# in9-test-board-v1.net
KiCad netlist of a schematic drawn in EAGLE
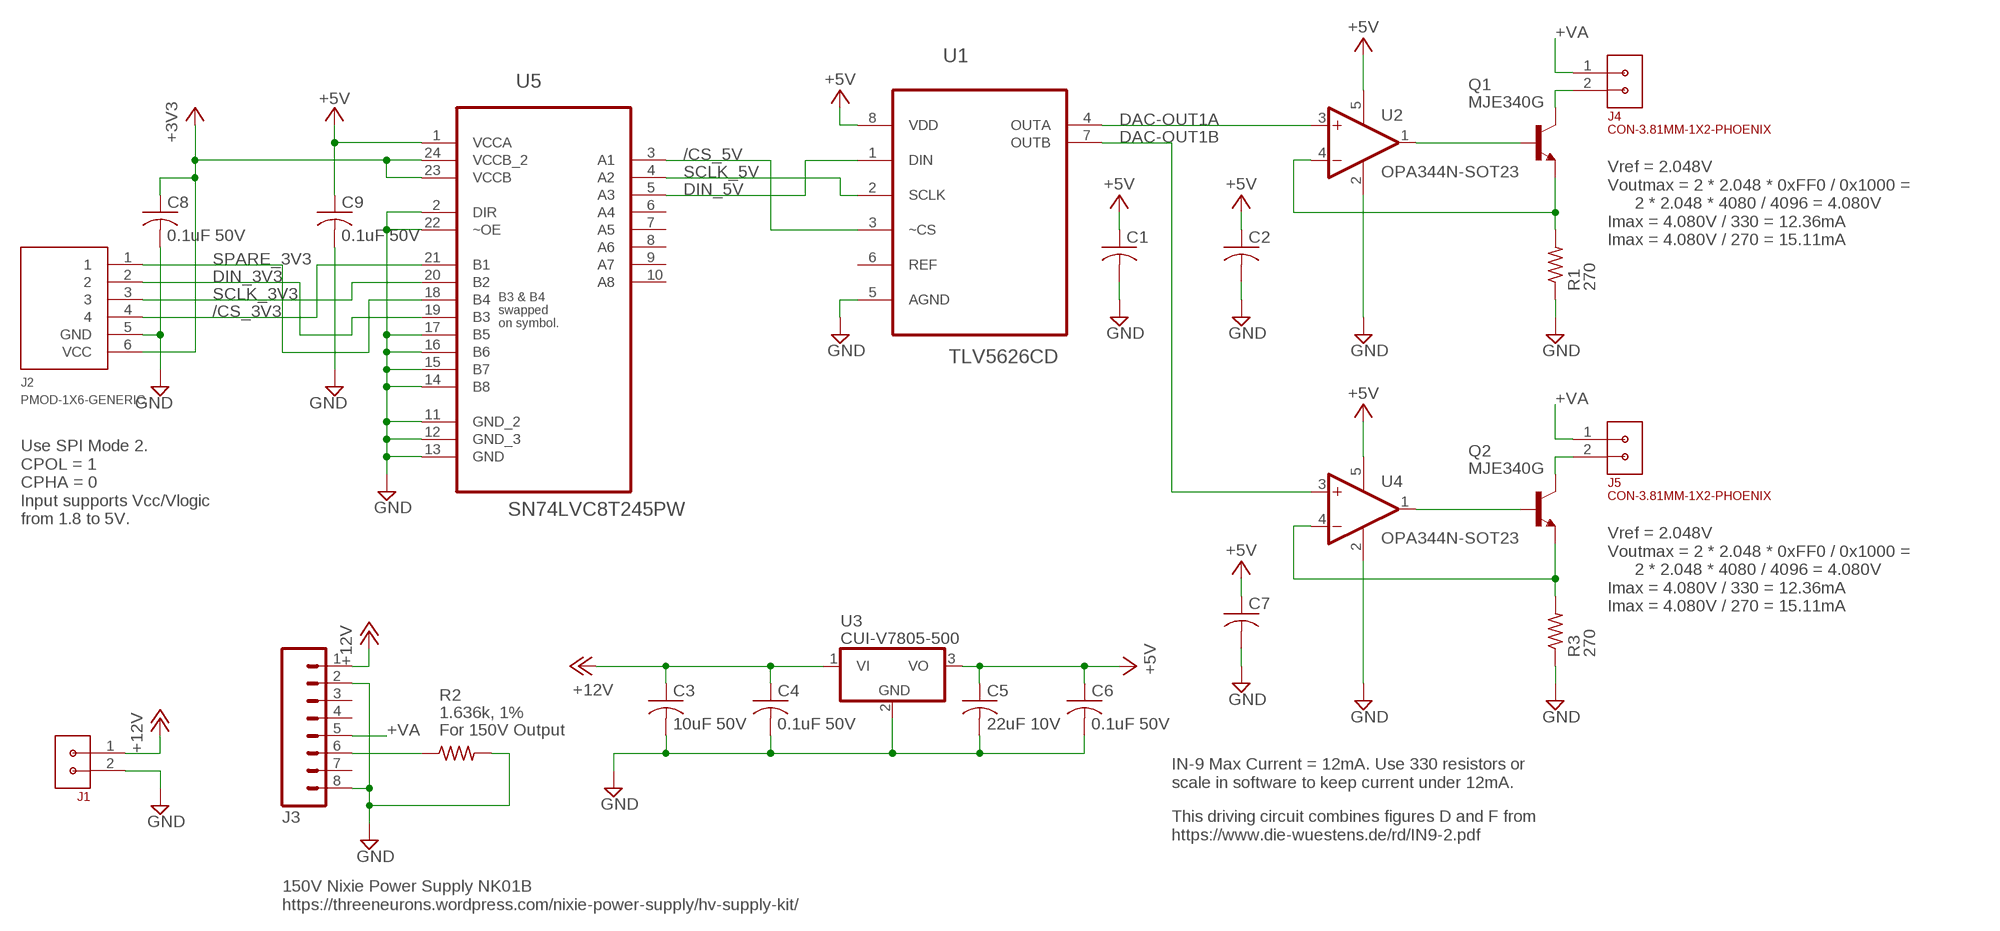
[diagram p0: schematic, sheet 1]

(export (version "E")
  (design (tool "Eeschema 10.0.6"))
  (components
    (comp (ref "C1")
      (value "C-USC1206K")
      (footprint "eagle-import:C1206K")
      (libsource (lib "eagle-import") (part "C-USC1206K"))
    )
    (comp (ref "C2")
      (value "C-USC1206K")
      (footprint "eagle-import:C1206K")
      (libsource (lib "eagle-import") (part "C-USC1206K"))
    )
    (comp (ref "C3")
      (value "10uF 50V")
      (footprint "eagle-import:C1210K")
      (fields (field (name "MFR") "KEMET") (field (name "MFR_PART_NO") "C1210C106K5RACTU"))
      (libsource (lib "eagle-import") (part "C-USC1210K"))
    )
    (comp (ref "C4")
      (value "0.1uF 50V")
      (footprint "eagle-import:C1206K")
      (fields (field (name "MFR") "KEMET") (field (name "MFR_PART_NO") "C1206S104M5RACTU"))
      (libsource (lib "eagle-import") (part "C-USC1206K"))
    )
    (comp (ref "C5")
      (value "22uF 10V")
      (footprint "eagle-import:C1206K")
      (fields (field (name "MFR") "KEMET") (field (name "MFR_PART_NO") "C1206C226K8RAC7800"))
      (libsource (lib "eagle-import") (part "C-USC1206K"))
    )
    (comp (ref "C6")
      (value "0.1uF 50V")
      (footprint "eagle-import:C1206K")
      (fields (field (name "MFR") "KEMET") (field (name "MFR_PART_NO") "C1206S104M5RACTU"))
      (libsource (lib "eagle-import") (part "C-USC1206K"))
    )
    (comp (ref "C7")
      (value "C-USC1206K")
      (footprint "eagle-import:C1206K")
      (libsource (lib "eagle-import") (part "C-USC1206K"))
    )
    (comp (ref "C8")
      (value "0.1uF 50V")
      (footprint "eagle-import:C1206K")
      (fields (field (name "MFR") "KEMET") (field (name "MFR_PART_NO") "C1206S104M5RACTU"))
      (libsource (lib "eagle-import") (part "C-USC1206K"))
    )
    (comp (ref "C9")
      (value "0.1uF 50V")
      (footprint "eagle-import:C1206K")
      (fields (field (name "MFR") "KEMET") (field (name "MFR_PART_NO") "C1206S104M5RACTU"))
      (libsource (lib "eagle-import") (part "C-USC1206K"))
    )
    (comp (ref "J1")
      (value "CON-3.81MM-1X2-PHOENIX-1803426")
      (footprint "eagle-import:CON-PHOENIX-1803426-3.81-1X2")
      (libsource (lib "eagle-import") (part "CON-3.81MM-1X2-PHOENIX-1803426"))
    )
    (comp (ref "J2")
      (value "PMOD-1X6-GENERIC")
      (footprint "eagle-import:CON-PMOD-1X6")
      (libsource (lib "eagle-import") (part "PMOD-1X6-GENERIC"))
    )
    (comp (ref "J3")
      (value "M08")
      (footprint "eagle-import:1X08")
      (libsource (lib "eagle-import") (part "M08"))
    )
    (comp (ref "J4")
      (value "CON-3.81MM-1X2-PHOENIX")
      (footprint "eagle-import:CON-PHOENIX-3.81-1X2-RA")
      (libsource (lib "eagle-import") (part "CON-3.81MM-1X2-PHOENIX"))
    )
    (comp (ref "J5")
      (value "CON-3.81MM-1X2-PHOENIX")
      (footprint "eagle-import:CON-PHOENIX-3.81-1X2-RA")
      (libsource (lib "eagle-import") (part "CON-3.81MM-1X2-PHOENIX"))
    )
    (comp (ref "Q1")
      (value "MJE340G")
      (footprint "eagle-import:TO126V")
      (libsource (lib "eagle-import") (part "-NPN-TO126V"))
    )
    (comp (ref "Q2")
      (value "MJE340G")
      (footprint "eagle-import:TO126V")
      (libsource (lib "eagle-import") (part "-NPN-TO126V"))
    )
    (comp (ref "R1")
      (value "270")
      (footprint "eagle-import:R1206")
      (libsource (lib "eagle-import") (part "R-US_R1206"))
    )
    (comp (ref "R2")
      (value "1.636k, 1%")
      (footprint "eagle-import:R1206")
      (libsource (lib "eagle-import") (part "R-US_R1206"))
    )
    (comp (ref "R3")
      (value "270")
      (footprint "eagle-import:R1206")
      (libsource (lib "eagle-import") (part "R-US_R1206"))
    )
    (comp (ref "U1")
      (value "TLV5626CD")
      (footprint "eagle-import:SOIC127P600X175-8N")
      (libsource (lib "eagle-import") (part "TLV5626CD"))
    )
    (comp (ref "U2")
      (value "OPA344N-SOT23")
      (footprint "eagle-import:SOT23-5")
      (libsource (lib "eagle-import") (part "OPA-SOT23344N"))
    )
    (comp (ref "U3")
      (value "CUI-V7805-500")
      (footprint "eagle-import:CUI-78XX-500")
      (libsource (lib "eagle-import") (part "CUI-V7803-500"))
    )
    (comp (ref "U4")
      (value "OPA344N-SOT23")
      (footprint "eagle-import:SOT23-5")
      (libsource (lib "eagle-import") (part "OPA-SOT23344N"))
    )
    (comp (ref "U5")
      (value "SN74LVC8T245PW")
      (footprint "eagle-import:SOP65P640X120-24N")
      (fields (field (name "MPN") "SN74AVC8T245PW"))
      (libsource (lib "eagle-import") (part "SN74AVC8T245PW"))
    )
  )
  (nets
    (net (code "1") (name "+3V3") (class "Default")
      (node (ref "C8") (pin "1") (pinfunction "1_1") (pintype "passive"))
      (node (ref "J2") (pin "6") (pinfunction "VCC_6") (pintype "bidirectional"))
      (node (ref "U5") (pin "23") (pinfunction "VCCB_23") (pintype "power_in"))
      (node (ref "U5") (pin "24") (pinfunction "VCCB_2_24") (pintype "power_in"))
    )
    (net (code "2") (name "+5V") (class "Default")
      (node (ref "C1") (pin "1") (pinfunction "1_1") (pintype "passive"))
      (node (ref "C2") (pin "1") (pinfunction "1_1") (pintype "passive"))
      (node (ref "C5") (pin "1") (pinfunction "1_1") (pintype "passive"))
      (node (ref "C6") (pin "1") (pinfunction "1_1") (pintype "passive"))
      (node (ref "C7") (pin "1") (pinfunction "1_1") (pintype "passive"))
      (node (ref "C9") (pin "1") (pinfunction "1_1") (pintype "passive"))
      (node (ref "U1") (pin "8") (pinfunction "VDD_8") (pintype "power_in"))
      (node (ref "U2") (pin "5") (pinfunction "V+_5") (pintype "power_in"))
      (node (ref "U3") (pin "3") (pinfunction "VO_3") (pintype "passive"))
      (node (ref "U4") (pin "5") (pinfunction "V+_5") (pintype "power_in"))
      (node (ref "U5") (pin "1") (pinfunction "VCCA_1") (pintype "power_in"))
    )
    (net (code "3") (name "+12V") (class "Default")
      (node (ref "C3") (pin "1") (pinfunction "1_1") (pintype "passive"))
      (node (ref "C4") (pin "1") (pinfunction "1_1") (pintype "passive"))
      (node (ref "J1") (pin "1") (pinfunction "1_1") (pintype "bidirectional"))
      (node (ref "J3") (pin "1") (pinfunction "1_1") (pintype "passive"))
      (node (ref "U3") (pin "1") (pinfunction "VI_1") (pintype "input"))
    )
    (net (code "4") (name "/+VA") (class "Default")
      (node (ref "J3") (pin "5") (pinfunction "5_5") (pintype "passive"))
      (node (ref "J4") (pin "1") (pinfunction "1_1") (pintype "bidirectional"))
      (node (ref "J5") (pin "1") (pinfunction "1_1") (pintype "bidirectional"))
    )
    (net (code "5") (name "/DAC-OUT1A") (class "Default")
      (node (ref "U1") (pin "4") (pinfunction "OUTA_4") (pintype "output"))
      (node (ref "U2") (pin "3") (pinfunction "+IN_3") (pintype "input"))
    )
    (net (code "6") (name "/DAC-OUT1B") (class "Default")
      (node (ref "U1") (pin "7") (pinfunction "OUTB_7") (pintype "output"))
      (node (ref "U4") (pin "3") (pinfunction "+IN_3") (pintype "input"))
    )
    (net (code "7") (name "/DIN_3V3") (class "Default")
      (node (ref "J2") (pin "2") (pinfunction "2_2") (pintype "bidirectional"))
      (node (ref "U5") (pin "19") (pinfunction "B3_19") (pintype "bidirectional"))
    )
    (net (code "8") (name "/DIN_5V") (class "Default")
      (node (ref "U1") (pin "1") (pinfunction "DIN_1") (pintype "input"))
      (node (ref "U5") (pin "5") (pinfunction "A3_5") (pintype "bidirectional"))
    )
    (net (code "9") (name "/SCLK_3V3") (class "Default")
      (node (ref "J2") (pin "3") (pinfunction "3_3") (pintype "bidirectional"))
      (node (ref "U5") (pin "20") (pinfunction "B2_20") (pintype "bidirectional"))
    )
    (net (code "10") (name "/SCLK_5V") (class "Default")
      (node (ref "U1") (pin "2") (pinfunction "SCLK_2") (pintype "input"))
      (node (ref "U5") (pin "4") (pinfunction "A2_4") (pintype "bidirectional"))
    )
    (net (code "11") (name "/SPARE_3V3") (class "Default")
      (node (ref "J2") (pin "1") (pinfunction "1_1") (pintype "bidirectional"))
      (node (ref "U5") (pin "18") (pinfunction "B4_18") (pintype "bidirectional"))
    )
    (net (code "12") (name "/{slash}CS_3V3") (class "Default")
      (node (ref "J2") (pin "4") (pinfunction "4_4") (pintype "bidirectional"))
      (node (ref "U5") (pin "21") (pinfunction "B1_21") (pintype "bidirectional"))
    )
    (net (code "13") (name "/{slash}CS_5V") (class "Default")
      (node (ref "U1") (pin "3") (pinfunction "~{CS}_3") (pintype "input"))
      (node (ref "U5") (pin "3") (pinfunction "A1_3") (pintype "bidirectional"))
    )
    (net (code "14") (name "GND") (class "Default")
      (node (ref "C1") (pin "2") (pinfunction "2_2") (pintype "passive"))
      (node (ref "C2") (pin "2") (pinfunction "2_2") (pintype "passive"))
      (node (ref "C3") (pin "2") (pinfunction "2_2") (pintype "passive"))
      (node (ref "C4") (pin "2") (pinfunction "2_2") (pintype "passive"))
      (node (ref "C5") (pin "2") (pinfunction "2_2") (pintype "passive"))
      (node (ref "C6") (pin "2") (pinfunction "2_2") (pintype "passive"))
      (node (ref "C7") (pin "2") (pinfunction "2_2") (pintype "passive"))
      (node (ref "C8") (pin "2") (pinfunction "2_2") (pintype "passive"))
      (node (ref "C9") (pin "2") (pinfunction "2_2") (pintype "passive"))
      (node (ref "J1") (pin "2") (pinfunction "2_2") (pintype "bidirectional"))
      (node (ref "J2") (pin "5") (pinfunction "GND_5") (pintype "power_in"))
      (node (ref "J3") (pin "2") (pinfunction "2_2") (pintype "passive"))
      (node (ref "J3") (pin "8") (pinfunction "8_8") (pintype "passive"))
      (node (ref "R1") (pin "1") (pinfunction "1_1") (pintype "passive"))
      (node (ref "R2") (pin "2") (pinfunction "2_2") (pintype "passive"))
      (node (ref "R3") (pin "1") (pinfunction "1_1") (pintype "passive"))
      (node (ref "U1") (pin "5") (pinfunction "AGND_5") (pintype "passive"))
      (node (ref "U2") (pin "2") (pinfunction "V-_2") (pintype "power_in"))
      (node (ref "U3") (pin "2") (pinfunction "GND_2") (pintype "passive"))
      (node (ref "U4") (pin "2") (pinfunction "V-_2") (pintype "power_in"))
      (node (ref "U5") (pin "11") (pinfunction "GND_2_11") (pintype "passive"))
      (node (ref "U5") (pin "12") (pinfunction "GND_3_12") (pintype "passive"))
      (node (ref "U5") (pin "13") (pinfunction "GND_13") (pintype "passive"))
      (node (ref "U5") (pin "14") (pinfunction "B8_14") (pintype "bidirectional"))
      (node (ref "U5") (pin "15") (pinfunction "B7_15") (pintype "bidirectional"))
      (node (ref "U5") (pin "16") (pinfunction "B6_16") (pintype "bidirectional"))
      (node (ref "U5") (pin "17") (pinfunction "B5_17") (pintype "bidirectional"))
      (node (ref "U5") (pin "2") (pinfunction "DIR_2") (pintype "input"))
      (node (ref "U5") (pin "22") (pinfunction "~{OE}_22") (pintype "input"))
    )
    (net (code "15") (name "Net-(J3-Pad6)") (class "Default")
      (node (ref "J3") (pin "6") (pinfunction "6_6") (pintype "passive"))
      (node (ref "R2") (pin "1") (pinfunction "1_1") (pintype "passive"))
    )
    (net (code "16") (name "Net-(Q1-B)") (class "Default")
      (node (ref "Q1") (pin "3") (pinfunction "B_3") (pintype "passive"))
      (node (ref "U2") (pin "1") (pinfunction "OUT_1") (pintype "output"))
    )
    (net (code "17") (name "Net-(Q1-C)") (class "Default")
      (node (ref "J4") (pin "2") (pinfunction "2_2") (pintype "bidirectional"))
      (node (ref "Q1") (pin "2") (pinfunction "C_2") (pintype "passive"))
    )
    (net (code "18") (name "Net-(Q1-E)") (class "Default")
      (node (ref "Q1") (pin "1") (pinfunction "E_1") (pintype "passive"))
      (node (ref "R1") (pin "2") (pinfunction "2_2") (pintype "passive"))
      (node (ref "U2") (pin "4") (pinfunction "-IN_4") (pintype "input"))
    )
    (net (code "19") (name "Net-(Q2-B)") (class "Default")
      (node (ref "Q2") (pin "3") (pinfunction "B_3") (pintype "passive"))
      (node (ref "U4") (pin "1") (pinfunction "OUT_1") (pintype "output"))
    )
    (net (code "20") (name "Net-(Q2-C)") (class "Default")
      (node (ref "J5") (pin "2") (pinfunction "2_2") (pintype "bidirectional"))
      (node (ref "Q2") (pin "2") (pinfunction "C_2") (pintype "passive"))
    )
    (net (code "21") (name "Net-(Q2-E)") (class "Default")
      (node (ref "Q2") (pin "1") (pinfunction "E_1") (pintype "passive"))
      (node (ref "R3") (pin "2") (pinfunction "2_2") (pintype "passive"))
      (node (ref "U4") (pin "4") (pinfunction "-IN_4") (pintype "input"))
    )
    (net (code "22") (name "unconnected-(J3-Pad3)") (class "Default")
      (node (ref "J3") (pin "3") (pinfunction "3_3") (pintype "passive"))
    )
    (net (code "23") (name "unconnected-(J3-Pad4)") (class "Default")
      (node (ref "J3") (pin "4") (pinfunction "4_4") (pintype "passive"))
    )
    (net (code "24") (name "unconnected-(J3-Pad7)") (class "Default")
      (node (ref "J3") (pin "7") (pinfunction "7_7") (pintype "passive"))
    )
    (net (code "25") (name "unconnected-(U1-REF-Pad6)") (class "Default")
      (node (ref "U1") (pin "6") (pinfunction "REF_6") (pintype "input"))
    )
    (net (code "26") (name "unconnected-(U5-A4-Pad6)") (class "Default")
      (node (ref "U5") (pin "6") (pinfunction "A4_6") (pintype "bidirectional"))
    )
    (net (code "27") (name "unconnected-(U5-A5-Pad7)") (class "Default")
      (node (ref "U5") (pin "7") (pinfunction "A5_7") (pintype "bidirectional"))
    )
    (net (code "28") (name "unconnected-(U5-A6-Pad8)") (class "Default")
      (node (ref "U5") (pin "8") (pinfunction "A6_8") (pintype "bidirectional"))
    )
    (net (code "29") (name "unconnected-(U5-A7-Pad9)") (class "Default")
      (node (ref "U5") (pin "9") (pinfunction "A7_9") (pintype "bidirectional"))
    )
    (net (code "30") (name "unconnected-(U5-A8-Pad10)") (class "Default")
      (node (ref "U5") (pin "10") (pinfunction "A8_10") (pintype "bidirectional"))
    )
  )
)
